# pos_sys.net
KiCad netlist of a schematic drawn in EAGLE
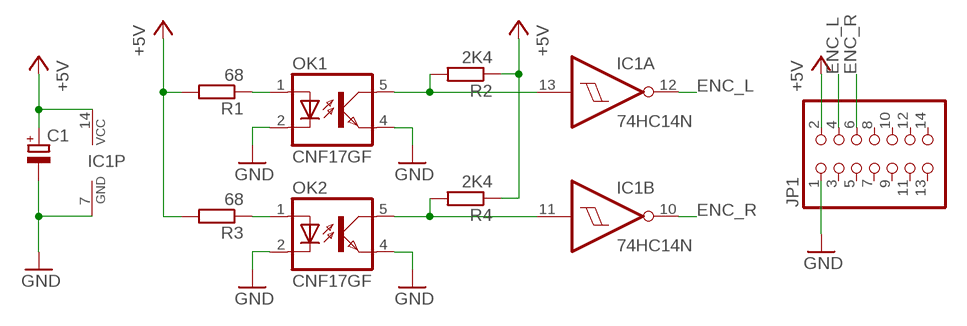
[diagram p0: schematic, sheet 1]

(export (version "E")
  (design (tool "Eeschema 10.0.6"))
  (components
    (comp (ref "C1")
      (value "CPOL-EUB45181C")
      (footprint "eagle-import:B45181C")
      (libsource (lib "eagle-import") (part "CPOL-EUB45181C"))
    )
    (comp (ref "IC1")
      (value "74HC14N")
      (footprint "eagle-import:DIL14")
      (libsource (lib "eagle-import") (part "7414NHC"))
    )
    (comp (ref "JP1")
      (value "PINHD-2X7")
      (footprint "eagle-import:2X07")
      (libsource (lib "eagle-import") (part "PINHD-2X7"))
    )
    (comp (ref "OK1")
      (value "CNF17GF")
      (footprint "eagle-import:DIL06B")
      (libsource (lib "eagle-import") (part "CNF17GF"))
    )
    (comp (ref "OK2")
      (value "CNF17GF")
      (footprint "eagle-import:DIL06B")
      (libsource (lib "eagle-import") (part "CNF17GF"))
    )
    (comp (ref "R1")
      (value "68")
      (footprint "eagle-import:0204_7")
      (libsource (lib "eagle-import") (part "R-EU_0204/7"))
    )
    (comp (ref "R2")
      (value "2K4")
      (footprint "eagle-import:0204_7")
      (libsource (lib "eagle-import") (part "R-EU_0204/7"))
    )
    (comp (ref "R3")
      (value "68")
      (footprint "eagle-import:0204_7")
      (libsource (lib "eagle-import") (part "R-EU_0204/7"))
    )
    (comp (ref "R4")
      (value "2K4")
      (footprint "eagle-import:0204_7")
      (libsource (lib "eagle-import") (part "R-EU_0204/7"))
    )
  )
  (nets
    (net (code "1") (name "+5V") (class "Default")
      (node (ref "C1") (pin "+") (pinfunction "+_+") (pintype "passive"))
      (node (ref "IC1") (pin "14") (pinfunction "VCC_14") (pintype "power_in"))
      (node (ref "JP1") (pin "2") (pinfunction "2_2") (pintype "passive"))
      (node (ref "R1") (pin "2") (pinfunction "2_2") (pintype "passive"))
      (node (ref "R2") (pin "1") (pinfunction "1_1") (pintype "passive"))
      (node (ref "R3") (pin "2") (pinfunction "2_2") (pintype "passive"))
      (node (ref "R4") (pin "1") (pinfunction "1_1") (pintype "passive"))
    )
    (net (code "2") (name "/ENC_L") (class "Default")
      (node (ref "IC1") (pin "12") (pinfunction "O_12") (pintype "output"))
      (node (ref "JP1") (pin "4") (pinfunction "4_4") (pintype "passive"))
    )
    (net (code "3") (name "/ENC_R") (class "Default")
      (node (ref "IC1") (pin "10") (pinfunction "O_10") (pintype "output"))
      (node (ref "JP1") (pin "6") (pinfunction "6_6") (pintype "passive"))
    )
    (net (code "4") (name "GND") (class "Default")
      (node (ref "C1") (pin "-") (pinfunction "-_-") (pintype "passive"))
      (node (ref "IC1") (pin "7") (pinfunction "GND_7") (pintype "power_in"))
      (node (ref "JP1") (pin "1") (pinfunction "1_1") (pintype "passive"))
      (node (ref "OK1") (pin "2") (pinfunction "C_2") (pintype "passive"))
      (node (ref "OK1") (pin "4") (pinfunction "EMIT_4") (pintype "passive"))
      (node (ref "OK2") (pin "2") (pinfunction "C_2") (pintype "passive"))
      (node (ref "OK2") (pin "4") (pinfunction "EMIT_4") (pintype "passive"))
    )
    (net (code "5") (name "Net-(IC1A-I)") (class "Default")
      (node (ref "IC1") (pin "13") (pinfunction "I_13") (pintype "input"))
      (node (ref "OK1") (pin "5") (pinfunction "COL_5") (pintype "passive"))
      (node (ref "R2") (pin "2") (pinfunction "2_2") (pintype "passive"))
    )
    (net (code "6") (name "Net-(IC1B-I)") (class "Default")
      (node (ref "IC1") (pin "11") (pinfunction "I_11") (pintype "input"))
      (node (ref "OK2") (pin "5") (pinfunction "COL_5") (pintype "passive"))
      (node (ref "R4") (pin "2") (pinfunction "2_2") (pintype "passive"))
    )
    (net (code "7") (name "Net-(OK1-A)") (class "Default")
      (node (ref "OK1") (pin "1") (pinfunction "A_1") (pintype "passive"))
      (node (ref "R1") (pin "1") (pinfunction "1_1") (pintype "passive"))
    )
    (net (code "8") (name "Net-(OK2-A)") (class "Default")
      (node (ref "OK2") (pin "1") (pinfunction "A_1") (pintype "passive"))
      (node (ref "R3") (pin "1") (pinfunction "1_1") (pintype "passive"))
    )
    (net (code "9") (name "unconnected-(JP1-Pad3)") (class "Default")
      (node (ref "JP1") (pin "3") (pinfunction "3_3") (pintype "passive"))
    )
    (net (code "10") (name "unconnected-(JP1-Pad5)") (class "Default")
      (node (ref "JP1") (pin "5") (pinfunction "5_5") (pintype "passive"))
    )
    (net (code "11") (name "unconnected-(JP1-Pad7)") (class "Default")
      (node (ref "JP1") (pin "7") (pinfunction "7_7") (pintype "passive"))
    )
    (net (code "12") (name "unconnected-(JP1-Pad8)") (class "Default")
      (node (ref "JP1") (pin "8") (pinfunction "8_8") (pintype "passive"))
    )
    (net (code "13") (name "unconnected-(JP1-Pad9)") (class "Default")
      (node (ref "JP1") (pin "9") (pinfunction "9_9") (pintype "passive"))
    )
    (net (code "14") (name "unconnected-(JP1-Pad10)") (class "Default")
      (node (ref "JP1") (pin "10") (pinfunction "10_10") (pintype "passive"))
    )
    (net (code "15") (name "unconnected-(JP1-Pad11)") (class "Default")
      (node (ref "JP1") (pin "11") (pinfunction "11_11") (pintype "passive"))
    )
    (net (code "16") (name "unconnected-(JP1-Pad12)") (class "Default")
      (node (ref "JP1") (pin "12") (pinfunction "12_12") (pintype "passive"))
    )
    (net (code "17") (name "unconnected-(JP1-Pad13)") (class "Default")
      (node (ref "JP1") (pin "13") (pinfunction "13_13") (pintype "passive"))
    )
    (net (code "18") (name "unconnected-(JP1-Pad14)") (class "Default")
      (node (ref "JP1") (pin "14") (pinfunction "14_14") (pintype "passive"))
    )
  )
)
